# FlyballETS-LIGHTS.net
KiCad netlist of a schematic drawn in EAGLE
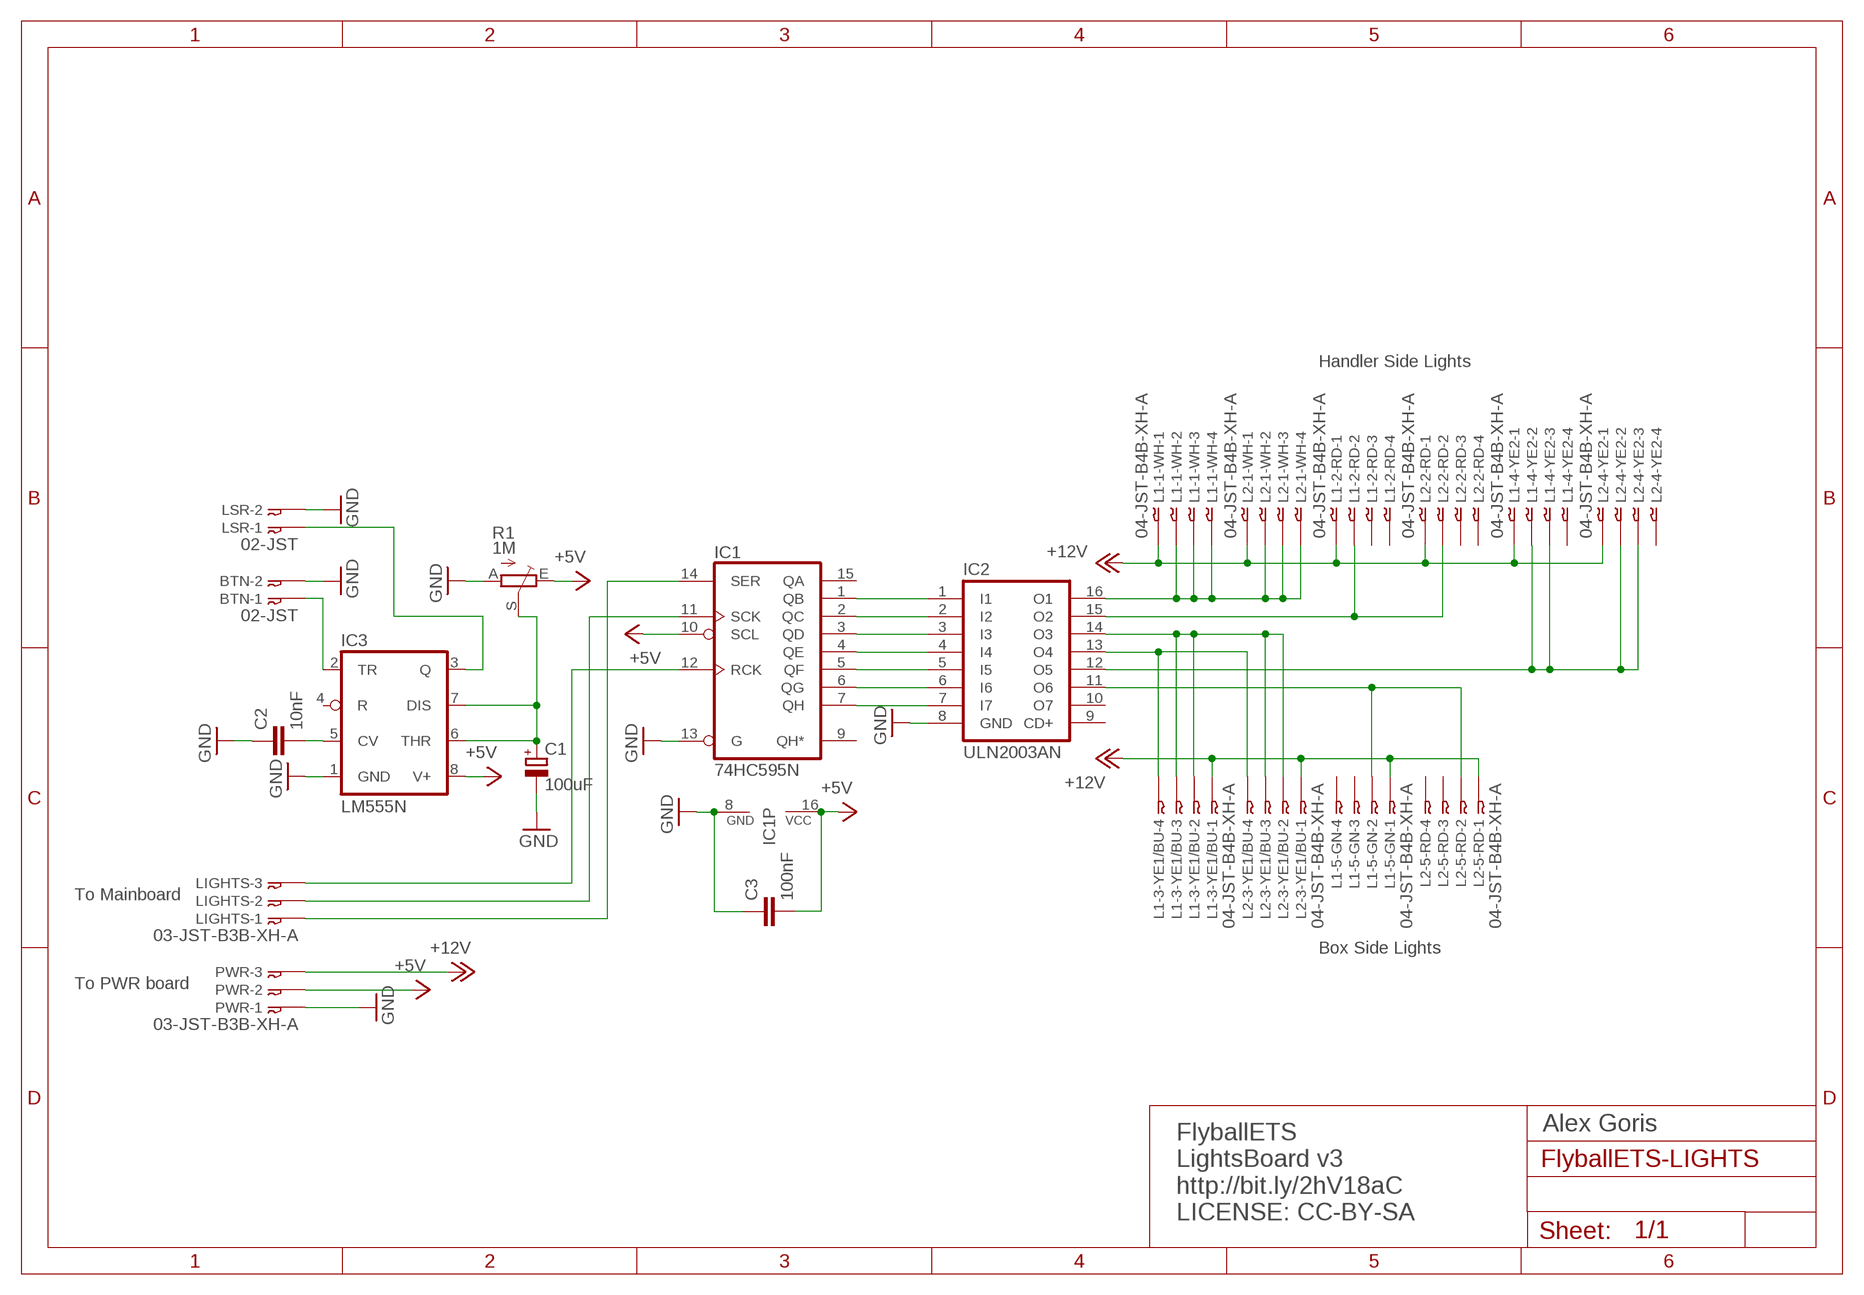
[diagram p0: schematic, sheet 1]

(export (version "E")
  (design (tool "Eeschema 10.0.6"))
  (components
    (comp (ref "BTN")
      (value "02-JST")
      (footprint "eagle-import:B2B-XH")
      (libsource (lib "eagle-import") (part "02-JST"))
    )
    (comp (ref "C1")
      (value "100uF")
      (footprint "eagle-import:E2,5-7")
      (libsource (lib "eagle-import") (part "CPOL-EUE2.5-7"))
    )
    (comp (ref "C2")
      (value "10nF")
      (footprint "eagle-import:C050-030X075")
      (libsource (lib "eagle-import") (part "C-EU050-030X075"))
    )
    (comp (ref "C3")
      (value "100nF")
      (footprint "eagle-import:C050-030X075")
      (libsource (lib "eagle-import") (part "C-EU050-030X075"))
    )
    (comp (ref "IC1")
      (value "74HC595N")
      (footprint "eagle-import:DIL16")
      (libsource (lib "eagle-import") (part "74595NHC"))
    )
    (comp (ref "IC2")
      (value "ULN2003AN")
      (footprint "eagle-import:DIL16")
      (libsource (lib "eagle-import") (part "ULN2003AN"))
    )
    (comp (ref "IC3")
      (value "LM555N")
      (footprint "eagle-import:DIL08")
      (libsource (lib "eagle-import") (part "555NLM"))
    )
    (comp (ref "L1-1-WH")
      (value "04-JST-B4B-XH-A")
      (footprint "eagle-import:B4B-XH")
      (libsource (lib "eagle-import") (part "04-JST-B4B-XH-A"))
    )
    (comp (ref "L1-2-RD")
      (value "04-JST-B4B-XH-A")
      (footprint "eagle-import:B4B-XH")
      (libsource (lib "eagle-import") (part "04-JST-B4B-XH-A"))
    )
    (comp (ref "L1-3-YE1/BU")
      (value "04-JST-B4B-XH-A")
      (footprint "eagle-import:B4B-XH")
      (libsource (lib "eagle-import") (part "04-JST-B4B-XH-A"))
    )
    (comp (ref "L1-4-YE2")
      (value "04-JST-B4B-XH-A")
      (footprint "eagle-import:B4B-XH")
      (libsource (lib "eagle-import") (part "04-JST-B4B-XH-A"))
    )
    (comp (ref "L1-5-GN")
      (value "04-JST-B4B-XH-A")
      (footprint "eagle-import:B4B-XH")
      (libsource (lib "eagle-import") (part "04-JST-B4B-XH-A"))
    )
    (comp (ref "L2-1-WH")
      (value "04-JST-B4B-XH-A")
      (footprint "eagle-import:B4B-XH")
      (libsource (lib "eagle-import") (part "04-JST-B4B-XH-A"))
    )
    (comp (ref "L2-2-RD")
      (value "04-JST-B4B-XH-A")
      (footprint "eagle-import:B4B-XH")
      (libsource (lib "eagle-import") (part "04-JST-B4B-XH-A"))
    )
    (comp (ref "L2-3-YE1/BU")
      (value "04-JST-B4B-XH-A")
      (footprint "eagle-import:B4B-XH")
      (libsource (lib "eagle-import") (part "04-JST-B4B-XH-A"))
    )
    (comp (ref "L2-4-YE2")
      (value "04-JST-B4B-XH-A")
      (footprint "eagle-import:B4B-XH")
      (libsource (lib "eagle-import") (part "04-JST-B4B-XH-A"))
    )
    (comp (ref "L2-5-RD")
      (value "04-JST-B4B-XH-A")
      (footprint "eagle-import:B4B-XH")
      (libsource (lib "eagle-import") (part "04-JST-B4B-XH-A"))
    )
    (comp (ref "LIGHTS")
      (value "03-JST-B3B-XH-A")
      (footprint "eagle-import:B3B-XH")
      (libsource (lib "eagle-import") (part "03-JST-B3B-XH-A"))
    )
    (comp (ref "LSR")
      (value "02-JST")
      (footprint "eagle-import:B2B-XH")
      (libsource (lib "eagle-import") (part "02-JST"))
    )
    (comp (ref "PWR")
      (value "03-JST-B3B-XH-A")
      (footprint "eagle-import:B3B-XH")
      (libsource (lib "eagle-import") (part "03-JST-B3B-XH-A"))
    )
    (comp (ref "R1")
      (value "1M")
      (footprint "eagle-import:B25P")
      (libsource (lib "eagle-import") (part "TRIM_EU-B25P"))
    )
  )
  (nets
    (net (code "1") (name "+5V") (class "Default")
      (node (ref "C3") (pin "2") (pinfunction "2_2") (pintype "passive"))
      (node (ref "IC1") (pin "10") (pinfunction "SCL_10") (pintype "input"))
      (node (ref "IC1") (pin "16") (pinfunction "VCC_16") (pintype "power_in"))
      (node (ref "IC3") (pin "8") (pinfunction "V+_8") (pintype "power_in"))
      (node (ref "PWR") (pin "P$2") (pinfunction "1_P$2") (pintype "passive"))
      (node (ref "R1") (pin "E") (pinfunction "E_E") (pintype "passive"))
    )
    (net (code "2") (name "+12V") (class "Default")
      (node (ref "L1-1-WH") (pin "P$1") (pinfunction "1_P$1") (pintype "passive"))
      (node (ref "L1-2-RD") (pin "P$1") (pinfunction "1_P$1") (pintype "passive"))
      (node (ref "L1-3-YE1/BU") (pin "P$1") (pinfunction "1_P$1") (pintype "passive"))
      (node (ref "L1-4-YE2") (pin "P$1") (pinfunction "1_P$1") (pintype "passive"))
      (node (ref "L1-5-GN") (pin "P$1") (pinfunction "1_P$1") (pintype "passive"))
      (node (ref "L2-1-WH") (pin "P$1") (pinfunction "1_P$1") (pintype "passive"))
      (node (ref "L2-2-RD") (pin "P$1") (pinfunction "1_P$1") (pintype "passive"))
      (node (ref "L2-3-YE1/BU") (pin "P$1") (pinfunction "1_P$1") (pintype "passive"))
      (node (ref "L2-4-YE2") (pin "P$1") (pinfunction "1_P$1") (pintype "passive"))
      (node (ref "L2-5-RD") (pin "P$1") (pinfunction "1_P$1") (pintype "passive"))
      (node (ref "PWR") (pin "P$3") (pinfunction "1_P$3") (pintype "passive"))
    )
    (net (code "3") (name "GND") (class "Default")
      (node (ref "BTN") (pin "P$2") (pinfunction "1_P$2") (pintype "passive"))
      (node (ref "C1") (pin "-") (pinfunction "-_-") (pintype "passive"))
      (node (ref "C2") (pin "1") (pinfunction "1_1") (pintype "passive"))
      (node (ref "C3") (pin "1") (pinfunction "1_1") (pintype "passive"))
      (node (ref "IC1") (pin "13") (pinfunction "G_13") (pintype "input"))
      (node (ref "IC1") (pin "8") (pinfunction "GND_8") (pintype "power_in"))
      (node (ref "IC2") (pin "8") (pinfunction "GND_8") (pintype "power_in"))
      (node (ref "IC3") (pin "1") (pinfunction "GND_1") (pintype "power_in"))
      (node (ref "LSR") (pin "P$2") (pinfunction "1_P$2") (pintype "passive"))
      (node (ref "PWR") (pin "P$1") (pinfunction "1_P$1") (pintype "passive"))
      (node (ref "R1") (pin "A") (pinfunction "A_A") (pintype "passive"))
    )
    (net (code "4") (name "Net-(BTNA-1)") (class "Default")
      (node (ref "BTN") (pin "P$1") (pinfunction "1_P$1") (pintype "passive"))
      (node (ref "IC3") (pin "2") (pinfunction "TR_2") (pintype "input"))
    )
    (net (code "5") (name "Net-(IC1A-QB)") (class "Default")
      (node (ref "IC1") (pin "1") (pinfunction "QB_1") (pintype "tri_state"))
      (node (ref "IC2") (pin "1") (pinfunction "I1_1") (pintype "input"))
    )
    (net (code "6") (name "Net-(IC1A-QC)") (class "Default")
      (node (ref "IC1") (pin "2") (pinfunction "QC_2") (pintype "tri_state"))
      (node (ref "IC2") (pin "2") (pinfunction "I2_2") (pintype "input"))
    )
    (net (code "7") (name "Net-(IC1A-QD)") (class "Default")
      (node (ref "IC1") (pin "3") (pinfunction "QD_3") (pintype "tri_state"))
      (node (ref "IC2") (pin "3") (pinfunction "I3_3") (pintype "input"))
    )
    (net (code "8") (name "Net-(IC1A-QE)") (class "Default")
      (node (ref "IC1") (pin "4") (pinfunction "QE_4") (pintype "tri_state"))
      (node (ref "IC2") (pin "4") (pinfunction "I4_4") (pintype "input"))
    )
    (net (code "9") (name "Net-(IC1A-QF)") (class "Default")
      (node (ref "IC1") (pin "5") (pinfunction "QF_5") (pintype "tri_state"))
      (node (ref "IC2") (pin "5") (pinfunction "I5_5") (pintype "input"))
    )
    (net (code "10") (name "Net-(IC1A-QG)") (class "Default")
      (node (ref "IC1") (pin "6") (pinfunction "QG_6") (pintype "tri_state"))
      (node (ref "IC2") (pin "6") (pinfunction "I6_6") (pintype "input"))
    )
    (net (code "11") (name "Net-(IC1A-QH)") (class "Default")
      (node (ref "IC1") (pin "7") (pinfunction "QH_7") (pintype "tri_state"))
      (node (ref "IC2") (pin "7") (pinfunction "I7_7") (pintype "input"))
    )
    (net (code "12") (name "Net-(IC1A-RCK)") (class "Default")
      (node (ref "IC1") (pin "12") (pinfunction "RCK_12") (pintype "input"))
      (node (ref "LIGHTS") (pin "P$3") (pinfunction "1_P$3") (pintype "passive"))
    )
    (net (code "13") (name "Net-(IC1A-SCK)") (class "Default")
      (node (ref "IC1") (pin "11") (pinfunction "SCK_11") (pintype "input"))
      (node (ref "LIGHTS") (pin "P$2") (pinfunction "1_P$2") (pintype "passive"))
    )
    (net (code "14") (name "Net-(IC1A-SER)") (class "Default")
      (node (ref "IC1") (pin "14") (pinfunction "SER_14") (pintype "input"))
      (node (ref "LIGHTS") (pin "P$1") (pinfunction "1_P$1") (pintype "passive"))
    )
    (net (code "15") (name "Net-(IC2-O1)") (class "Default")
      (node (ref "IC2") (pin "16") (pinfunction "O1_16") (pintype "open_collector"))
      (node (ref "L1-1-WH") (pin "P$2") (pinfunction "1_P$2") (pintype "passive"))
      (node (ref "L1-1-WH") (pin "P$3") (pinfunction "1_P$3") (pintype "passive"))
      (node (ref "L1-1-WH") (pin "P$4") (pinfunction "1_P$4") (pintype "passive"))
      (node (ref "L2-1-WH") (pin "P$2") (pinfunction "1_P$2") (pintype "passive"))
      (node (ref "L2-1-WH") (pin "P$3") (pinfunction "1_P$3") (pintype "passive"))
      (node (ref "L2-1-WH") (pin "P$4") (pinfunction "1_P$4") (pintype "passive"))
    )
    (net (code "16") (name "Net-(IC2-O2)") (class "Default")
      (node (ref "IC2") (pin "15") (pinfunction "O2_15") (pintype "open_collector"))
      (node (ref "L1-2-RD") (pin "P$2") (pinfunction "1_P$2") (pintype "passive"))
      (node (ref "L2-2-RD") (pin "P$2") (pinfunction "1_P$2") (pintype "passive"))
    )
    (net (code "17") (name "Net-(IC2-O3)") (class "Default")
      (node (ref "IC2") (pin "14") (pinfunction "O3_14") (pintype "open_collector"))
      (node (ref "L1-3-YE1/BU") (pin "P$2") (pinfunction "1_P$2") (pintype "passive"))
      (node (ref "L1-3-YE1/BU") (pin "P$3") (pinfunction "1_P$3") (pintype "passive"))
      (node (ref "L2-3-YE1/BU") (pin "P$2") (pinfunction "1_P$2") (pintype "passive"))
      (node (ref "L2-3-YE1/BU") (pin "P$3") (pinfunction "1_P$3") (pintype "passive"))
    )
    (net (code "18") (name "Net-(IC2-O4)") (class "Default")
      (node (ref "IC2") (pin "13") (pinfunction "O4_13") (pintype "open_collector"))
      (node (ref "L1-3-YE1/BU") (pin "P$4") (pinfunction "1_P$4") (pintype "passive"))
      (node (ref "L2-3-YE1/BU") (pin "P$4") (pinfunction "1_P$4") (pintype "passive"))
    )
    (net (code "19") (name "Net-(IC2-O5)") (class "Default")
      (node (ref "IC2") (pin "12") (pinfunction "O5_12") (pintype "open_collector"))
      (node (ref "L1-4-YE2") (pin "P$2") (pinfunction "1_P$2") (pintype "passive"))
      (node (ref "L1-4-YE2") (pin "P$3") (pinfunction "1_P$3") (pintype "passive"))
      (node (ref "L2-4-YE2") (pin "P$2") (pinfunction "1_P$2") (pintype "passive"))
      (node (ref "L2-4-YE2") (pin "P$3") (pinfunction "1_P$3") (pintype "passive"))
    )
    (net (code "20") (name "Net-(IC2-O6)") (class "Default")
      (node (ref "IC2") (pin "11") (pinfunction "O6_11") (pintype "open_collector"))
      (node (ref "L1-5-GN") (pin "P$2") (pinfunction "1_P$2") (pintype "passive"))
      (node (ref "L2-5-RD") (pin "P$2") (pinfunction "1_P$2") (pintype "passive"))
    )
    (net (code "21") (name "Net-(IC3-CV)") (class "Default")
      (node (ref "C2") (pin "2") (pinfunction "2_2") (pintype "passive"))
      (node (ref "IC3") (pin "5") (pinfunction "CV_5") (pintype "input"))
    )
    (net (code "22") (name "Net-(IC3-DIS)") (class "Default")
      (node (ref "C1") (pin "+") (pinfunction "+_+") (pintype "passive"))
      (node (ref "IC3") (pin "6") (pinfunction "THR_6") (pintype "input"))
      (node (ref "IC3") (pin "7") (pinfunction "DIS_7") (pintype "input"))
      (node (ref "R1") (pin "S") (pinfunction "S_S") (pintype "passive"))
    )
    (net (code "23") (name "Net-(IC3-Q)") (class "Default")
      (node (ref "IC3") (pin "3") (pinfunction "Q_3") (pintype "output"))
      (node (ref "LSR") (pin "P$1") (pinfunction "1_P$1") (pintype "passive"))
    )
    (net (code "24") (name "unconnected-(IC1A-QA-Pad15)") (class "Default")
      (node (ref "IC1") (pin "15") (pinfunction "QA_15") (pintype "tri_state"))
    )
    (net (code "25") (name "unconnected-(IC1A-QH*-Pad9)") (class "Default")
      (node (ref "IC1") (pin "9") (pinfunction "QH*_9") (pintype "tri_state"))
    )
    (net (code "26") (name "unconnected-(IC2-CD+-Pad9)") (class "Default")
      (node (ref "IC2") (pin "9") (pinfunction "CD+_9") (pintype "passive"))
    )
    (net (code "27") (name "unconnected-(IC2-O7-Pad10)") (class "Default")
      (node (ref "IC2") (pin "10") (pinfunction "O7_10") (pintype "open_collector"))
    )
    (net (code "28") (name "unconnected-(IC3-R-Pad4)") (class "Default")
      (node (ref "IC3") (pin "4") (pinfunction "R_4") (pintype "input"))
    )
    (net (code "29") (name "unconnected-(L1-2-RDC-1-PadP$3)") (class "Default")
      (node (ref "L1-2-RD") (pin "P$3") (pinfunction "1_P$3") (pintype "passive"))
    )
    (net (code "30") (name "unconnected-(L1-2-RDD-1-PadP$4)") (class "Default")
      (node (ref "L1-2-RD") (pin "P$4") (pinfunction "1_P$4") (pintype "passive"))
    )
    (net (code "31") (name "unconnected-(L1-4-YE2D-1-PadP$4)") (class "Default")
      (node (ref "L1-4-YE2") (pin "P$4") (pinfunction "1_P$4") (pintype "passive"))
    )
    (net (code "32") (name "unconnected-(L1-5-GNC-1-PadP$3)") (class "Default")
      (node (ref "L1-5-GN") (pin "P$3") (pinfunction "1_P$3") (pintype "passive"))
    )
    (net (code "33") (name "unconnected-(L1-5-GND-1-PadP$4)") (class "Default")
      (node (ref "L1-5-GN") (pin "P$4") (pinfunction "1_P$4") (pintype "passive"))
    )
    (net (code "34") (name "unconnected-(L2-2-RDC-1-PadP$3)") (class "Default")
      (node (ref "L2-2-RD") (pin "P$3") (pinfunction "1_P$3") (pintype "passive"))
    )
    (net (code "35") (name "unconnected-(L2-2-RDD-1-PadP$4)") (class "Default")
      (node (ref "L2-2-RD") (pin "P$4") (pinfunction "1_P$4") (pintype "passive"))
    )
    (net (code "36") (name "unconnected-(L2-4-YE2D-1-PadP$4)") (class "Default")
      (node (ref "L2-4-YE2") (pin "P$4") (pinfunction "1_P$4") (pintype "passive"))
    )
    (net (code "37") (name "unconnected-(L2-5-RDC-1-PadP$3)") (class "Default")
      (node (ref "L2-5-RD") (pin "P$3") (pinfunction "1_P$3") (pintype "passive"))
    )
    (net (code "38") (name "unconnected-(L2-5-RDD-1-PadP$4)") (class "Default")
      (node (ref "L2-5-RD") (pin "P$4") (pinfunction "1_P$4") (pintype "passive"))
    )
  )
)
